# TSC_Project_v30.net
KiCad netlist of a schematic drawn in EAGLE
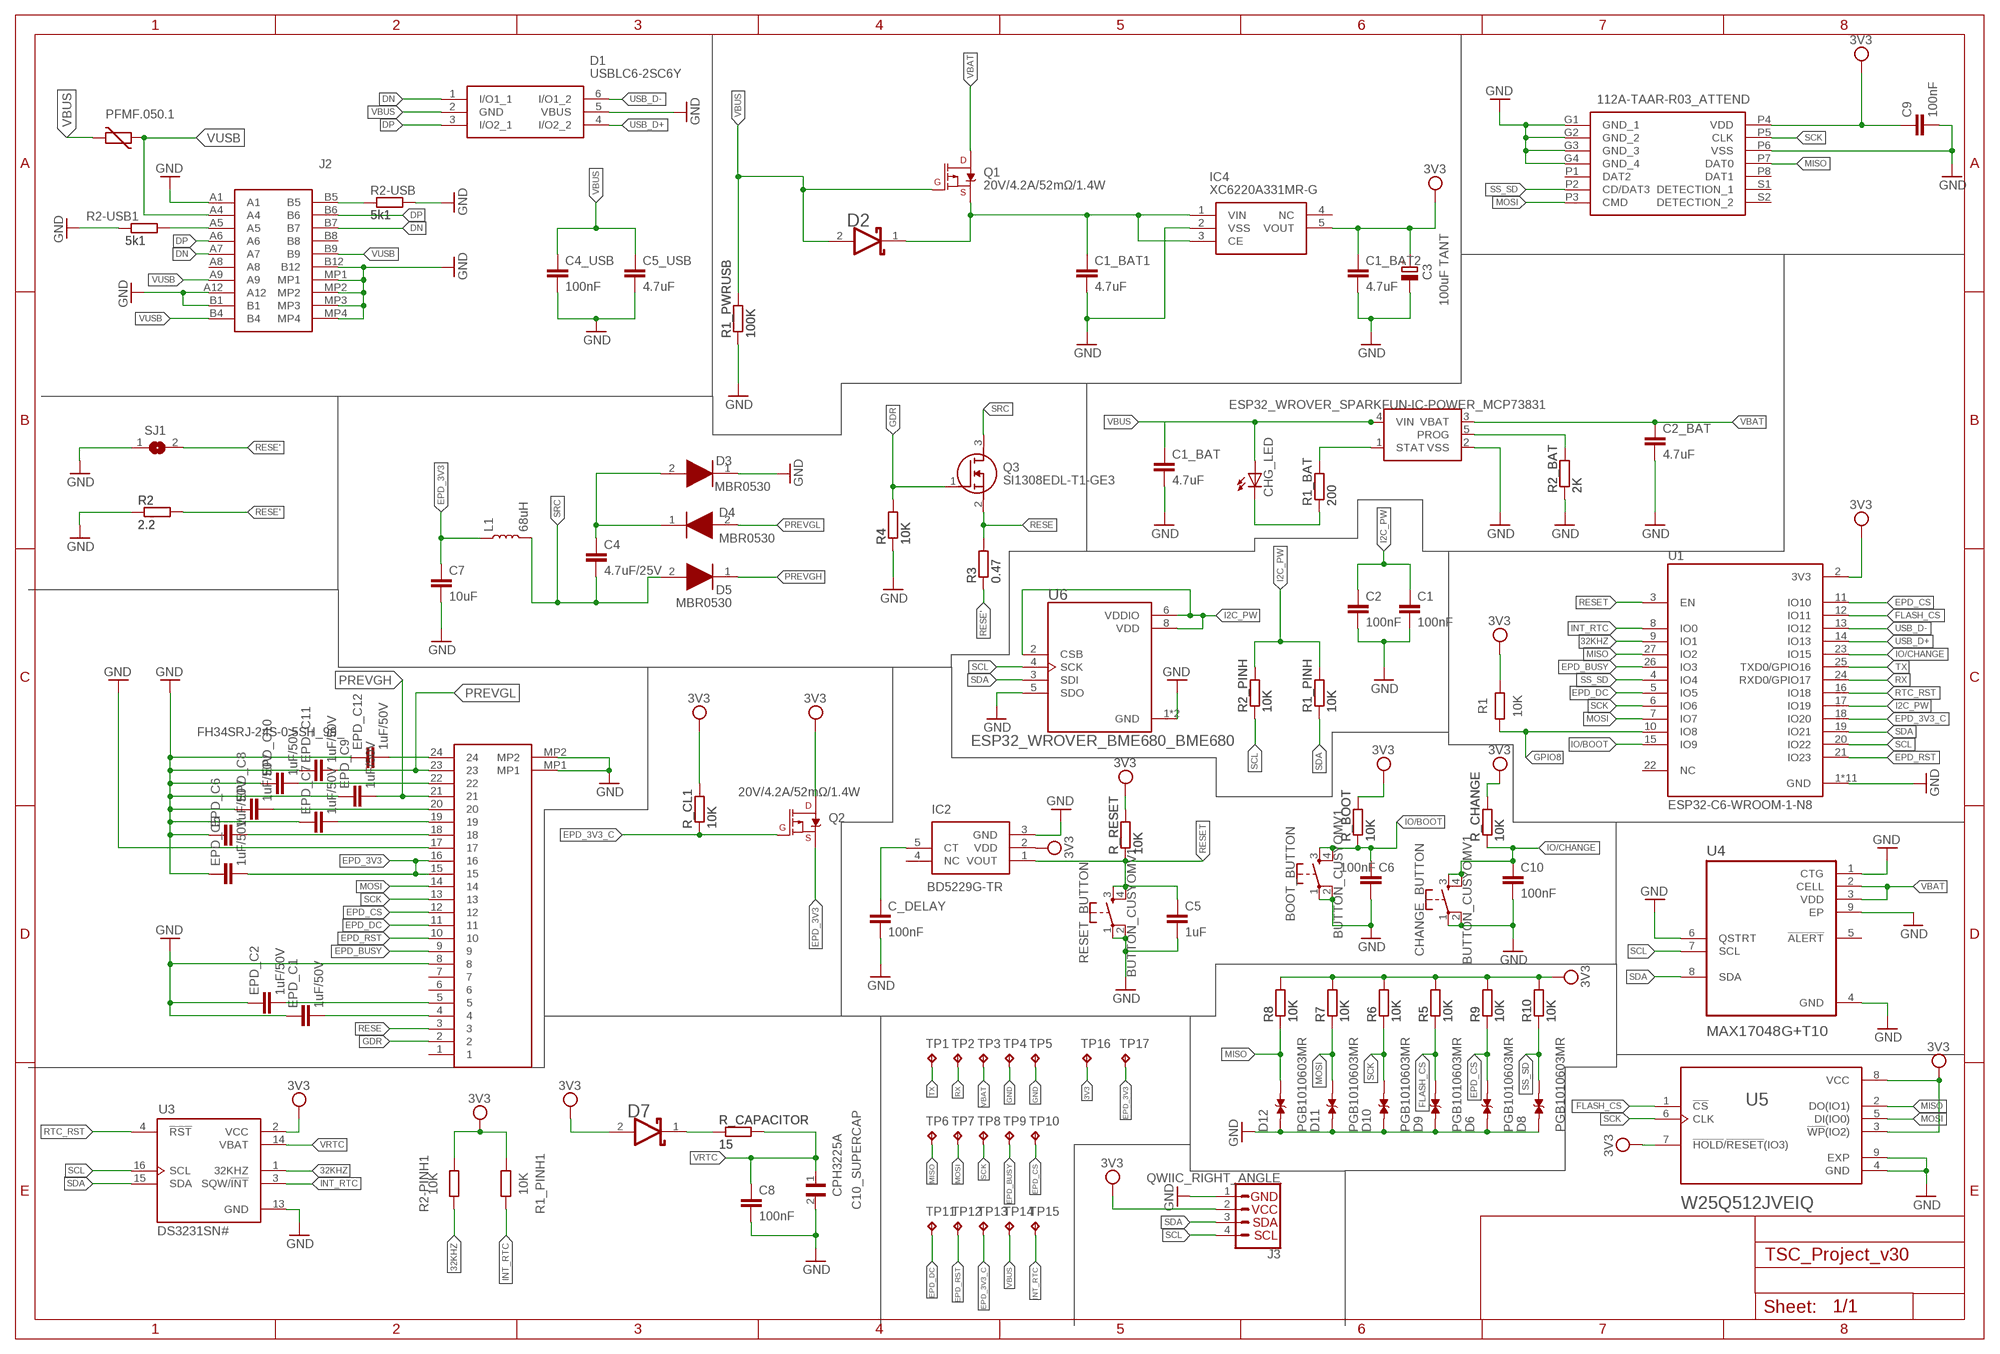
[diagram p0: schematic, sheet 1]

(export (version "E")
  (design (tool "Eeschema 10.0.6"))
  (components
    (comp (ref "BOOT_BUTTON")
      (value "BUTTON_CUSYOMV1")
      (footprint "eagle-import:MYBUTTON")
      (libsource (lib "eagle-import") (part "BUTTON_CUSYOMV1"))
    )
    (comp (ref "C1")
      (value "100nF")
      (footprint "eagle-import:ESP32_WROVER_EAGLE-LTSPICE_C0402")
      (libsource (lib "eagle-import") (part "ESP32_WROVER_EAGLE-LTSPICE_CC0402"))
    )
    (comp (ref "C1_BAT")
      (value "4.7uF")
      (footprint "eagle-import:ESP32_WROVER_EAGLE-LTSPICE_C0402")
      (libsource (lib "eagle-import") (part "ESP32_WROVER_EAGLE-LTSPICE_CC0402"))
    )
    (comp (ref "C1_BAT1")
      (value "4.7uF")
      (footprint "eagle-import:ESP32_WROVER_EAGLE-LTSPICE_C0402")
      (libsource (lib "eagle-import") (part "EAGLE-LTSPICE_CC0402"))
    )
    (comp (ref "C1_BAT2")
      (value "4.7uF")
      (footprint "eagle-import:ESP32_WROVER_EAGLE-LTSPICE_C0402")
      (libsource (lib "eagle-import") (part "EAGLE-LTSPICE_CC0402"))
    )
    (comp (ref "C2")
      (value "100nF")
      (footprint "eagle-import:ESP32_WROVER_EAGLE-LTSPICE_C0402")
      (libsource (lib "eagle-import") (part "ESP32_WROVER_EAGLE-LTSPICE_CC0402"))
    )
    (comp (ref "C2_BAT")
      (value "4.7uF")
      (footprint "eagle-import:ESP32_WROVER_EAGLE-LTSPICE_C0402")
      (libsource (lib "eagle-import") (part "ESP32_WROVER_EAGLE-LTSPICE_CC0402"))
    )
    (comp (ref "C3")
      (value "100uF TANT")
      (footprint "eagle-import:RCL_CT3528")
      (libsource (lib "eagle-import") (part "RCL_CPOL-EUCT3528"))
    )
    (comp (ref "C4")
      (value "4.7uF/25V")
      (footprint "eagle-import:ESP32_WROVER_EAGLE-LTSPICE_C0402")
      (libsource (lib "eagle-import") (part "ESP32_WROVER_EAGLE-LTSPICE_CC0402"))
    )
    (comp (ref "C4_USB")
      (value "100nF")
      (footprint "eagle-import:ESP32_WROVER_EAGLE-LTSPICE_C0402")
      (libsource (lib "eagle-import") (part "EAGLE-LTSPICE_CC0402"))
    )
    (comp (ref "C5")
      (value "1uF")
      (footprint "eagle-import:ESP32_WROVER_EAGLE-LTSPICE_C0402")
      (libsource (lib "eagle-import") (part "ESP32_WROVER_EAGLE-LTSPICE_CC0402"))
    )
    (comp (ref "C5_USB")
      (value "4.7uF")
      (footprint "eagle-import:ESP32_WROVER_EAGLE-LTSPICE_C0402")
      (libsource (lib "eagle-import") (part "EAGLE-LTSPICE_CC0402"))
    )
    (comp (ref "C6")
      (value "100nF")
      (footprint "eagle-import:ESP32_WROVER_EAGLE-LTSPICE_C0402")
      (libsource (lib "eagle-import") (part "ESP32_WROVER_EAGLE-LTSPICE_CC0402"))
    )
    (comp (ref "C7")
      (value "10uF")
      (footprint "eagle-import:ESP32_WROVER_EAGLE-LTSPICE_C0402")
      (libsource (lib "eagle-import") (part "ESP32_WROVER_EAGLE-LTSPICE_CC0402"))
    )
    (comp (ref "C8")
      (value "100nF")
      (footprint "eagle-import:ESP32_WROVER_EAGLE-LTSPICE_C0402")
      (libsource (lib "eagle-import") (part "ESP32_WROVER_EAGLE-LTSPICE_CC0402"))
    )
    (comp (ref "C9")
      (value "100nF")
      (footprint "eagle-import:ESP32_WROVER_EAGLE-LTSPICE_C0402")
      (libsource (lib "eagle-import") (part "ESP32_WROVER_EAGLE-LTSPICE_CC0402"))
    )
    (comp (ref "C10")
      (value "100nF")
      (footprint "eagle-import:ESP32_WROVER_EAGLE-LTSPICE_C0402")
      (libsource (lib "eagle-import") (part "ESP32_WROVER_EAGLE-LTSPICE_CC0402"))
    )
    (comp (ref "C10_SUPERCAP")
      (value "CPH3225A")
      (footprint "eagle-import:CAPCP3225X100N")
      (fields (field (name "MF") "Seiko Instruments"))
      (libsource (lib "eagle-import") (part "CPH3225A"))
    )
    (comp (ref "CHANGE_BUTTON")
      (value "BUTTON_CUSYOMV1")
      (footprint "eagle-import:MYBUTTON")
      (libsource (lib "eagle-import") (part "BUTTON_CUSYOMV1"))
    )
    (comp (ref "CHG_LED")
      (value "ADAFRUIT_LEDCHIP-LED0603")
      (footprint "eagle-import:ADAFRUIT_CHIP-LED0603")
      (libsource (lib "eagle-import") (part "ADAFRUIT_LEDCHIP-LED0603"))
    )
    (comp (ref "C_DELAY")
      (value "100nF")
      (footprint "eagle-import:ESP32_WROVER_EAGLE-LTSPICE_C0402")
      (libsource (lib "eagle-import") (part "EAGLE-LTSPICE_CC0402"))
    )
    (comp (ref "D1")
      (value "USBLC6-2SC6Y")
      (footprint "eagle-import:SOT95P280X145-6N")
      (fields (field (name "MF") "STMicroelectronics"))
      (libsource (lib "eagle-import") (part "USBLC6-2SC6Y"))
    )
    (comp (ref "D2")
      (value "ESP32_WROVER_AVX---SD0805S020S1R0_AVX_SD0805S020S1R0_0_0AVX_SD0805S020S1R0_0_0")
      (footprint "eagle-import:ESP32_WROVER_AVX---SD0805S020S1R0_AVX_SD0805S020S1R0_0")
      (fields
        (field (name "DIGIKEY_PART_NUMBER") "478-7800-1-ND")
        (field (name "MF") "AVX")
        (field (name "MOUSER_PART_NUMBER") "581-SD0805S020S1R0")
      )
      (libsource (lib "eagle-import") (part "ESP32_WROVER_AVX---SD0805S020S1R0_AVX_SD0805S020S1R0_0_0AVX_SD0805S020S1R0_0_0"))
    )
    (comp (ref "D3")
      (value "MBR0530")
      (footprint "eagle-import:SOD3716X135N")
      (fields (field (name "MF") "ON Semiconductor"))
      (libsource (lib "eagle-import") (part "MBR0530"))
    )
    (comp (ref "D4")
      (value "MBR0530")
      (footprint "eagle-import:SOD3716X135N")
      (fields (field (name "MF") "ON Semiconductor"))
      (libsource (lib "eagle-import") (part "MBR0530"))
    )
    (comp (ref "D5")
      (value "MBR0530")
      (footprint "eagle-import:SOD3716X135N")
      (fields (field (name "MF") "ON Semiconductor"))
      (libsource (lib "eagle-import") (part "MBR0530"))
    )
    (comp (ref "D6")
      (value "PGB1010603MR")
      (footprint "eagle-import:DIOC1608X36N")
      (fields (field (name "MF") "Littelfuse Inc."))
      (libsource (lib "eagle-import") (part "PGB1010603MR"))
    )
    (comp (ref "D7")
      (value "ESP32_WROVER_AVX---SD0805S020S1R0_AVX_SD0805S020S1R0_0_0AVX_SD0805S020S1R0_0_0")
      (footprint "eagle-import:ESP32_WROVER_AVX---SD0805S020S1R0_AVX_SD0805S020S1R0_0")
      (fields
        (field (name "DIGIKEY_PART_NUMBER") "478-7800-1-ND")
        (field (name "MF") "AVX")
        (field (name "MOUSER_PART_NUMBER") "581-SD0805S020S1R0")
      )
      (libsource (lib "eagle-import") (part "ESP32_WROVER_AVX---SD0805S020S1R0_AVX_SD0805S020S1R0_0_0AVX_SD0805S020S1R0_0_0"))
    )
    (comp (ref "D8")
      (value "PGB1010603MR")
      (footprint "eagle-import:DIOC1608X36N")
      (fields (field (name "MF") "Littelfuse Inc."))
      (libsource (lib "eagle-import") (part "PGB1010603MR"))
    )
    (comp (ref "D9")
      (value "PGB1010603MR")
      (footprint "eagle-import:DIOC1608X36N")
      (fields (field (name "MF") "Littelfuse Inc."))
      (libsource (lib "eagle-import") (part "PGB1010603MR"))
    )
    (comp (ref "D10")
      (value "PGB1010603MR")
      (footprint "eagle-import:DIOC1608X36N")
      (fields (field (name "MF") "Littelfuse Inc."))
      (libsource (lib "eagle-import") (part "PGB1010603MR"))
    )
    (comp (ref "D11")
      (value "PGB1010603MR")
      (footprint "eagle-import:DIOC1608X36N")
      (fields (field (name "MF") "Littelfuse Inc."))
      (libsource (lib "eagle-import") (part "PGB1010603MR"))
    )
    (comp (ref "D12")
      (value "PGB1010603MR")
      (footprint "eagle-import:DIOC1608X36N")
      (fields (field (name "MF") "Littelfuse Inc."))
      (libsource (lib "eagle-import") (part "PGB1010603MR"))
    )
    (comp (ref "EPD_C1")
      (value "1uF/50V")
      (footprint "eagle-import:ESP32_WROVER_EAGLE-LTSPICE_C0402")
      (libsource (lib "eagle-import") (part "ESP32_WROVER_EAGLE-LTSPICE_CC0402"))
    )
    (comp (ref "EPD_C2")
      (value "1uF/50V")
      (footprint "eagle-import:ESP32_WROVER_EAGLE-LTSPICE_C0402")
      (libsource (lib "eagle-import") (part "ESP32_WROVER_EAGLE-LTSPICE_CC0402"))
    )
    (comp (ref "EPD_C5")
      (value "1uF/50V")
      (footprint "eagle-import:ESP32_WROVER_EAGLE-LTSPICE_C0402")
      (libsource (lib "eagle-import") (part "ESP32_WROVER_EAGLE-LTSPICE_CC0402"))
    )
    (comp (ref "EPD_C6")
      (value "1uF/50V")
      (footprint "eagle-import:ESP32_WROVER_EAGLE-LTSPICE_C0402")
      (libsource (lib "eagle-import") (part "ESP32_WROVER_EAGLE-LTSPICE_CC0402"))
    )
    (comp (ref "EPD_C7")
      (value "1uF/50V")
      (footprint "eagle-import:ESP32_WROVER_EAGLE-LTSPICE_C0402")
      (libsource (lib "eagle-import") (part "ESP32_WROVER_EAGLE-LTSPICE_CC0402"))
    )
    (comp (ref "EPD_C8")
      (value "1uF/50V")
      (footprint "eagle-import:ESP32_WROVER_EAGLE-LTSPICE_C0402")
      (libsource (lib "eagle-import") (part "ESP32_WROVER_EAGLE-LTSPICE_CC0402"))
    )
    (comp (ref "EPD_C9")
      (value "1uF/50V")
      (footprint "eagle-import:ESP32_WROVER_EAGLE-LTSPICE_C0402")
      (libsource (lib "eagle-import") (part "ESP32_WROVER_EAGLE-LTSPICE_CC0402"))
    )
    (comp (ref "EPD_C10")
      (value "1uF/50V")
      (footprint "eagle-import:ESP32_WROVER_EAGLE-LTSPICE_C0402")
      (libsource (lib "eagle-import") (part "ESP32_WROVER_EAGLE-LTSPICE_CC0402"))
    )
    (comp (ref "EPD_C11")
      (value "1uF/50V")
      (footprint "eagle-import:ESP32_WROVER_EAGLE-LTSPICE_C0402")
      (libsource (lib "eagle-import") (part "ESP32_WROVER_EAGLE-LTSPICE_CC0402"))
    )
    (comp (ref "EPD_C12")
      (value "1uF/50V")
      (footprint "eagle-import:ESP32_WROVER_EAGLE-LTSPICE_C0402")
      (libsource (lib "eagle-import") (part "ESP32_WROVER_EAGLE-LTSPICE_CC0402"))
    )
    (comp (ref "IC2")
      (value "BD5229G-TR")
      (footprint "eagle-import:SOT95P280X125-5N")
      (fields (field (name "MOUSER_PART_NUMBER") "755-BD5229G-TR"))
      (libsource (lib "eagle-import") (part "BD5229G-TR"))
    )
    (comp (ref "IC4")
      (value "XC6220A331MR-G")
      (footprint "eagle-import:SOT95P280X120-5N")
      (fields (field (name "MOUSER_PART_NUMBER") "865-XC6220A331MR-G"))
      (libsource (lib "eagle-import") (part "XC6220A331MR-G"))
    )
    (comp (ref "J1")
      (value "FH34SRJ-24S-0.5SH_99_")
      (footprint "eagle-import:FH34SRJ24S05SH99")
      (fields
        (field (name "MANUFACTURER_PART_NUMBER") "FH34SRJ-24S-0.5SH(99)")
        (field (name "MOUSER_PART_NUMBER") "798-FH34SRJ24S05SH99")
      )
      (libsource (lib "eagle-import") (part "FH34SRJ-24S-0.5SH_99_"))
    )
    (comp (ref "J2")
      (value "SAMACSYS_PARTS_USB4110-GF-A")
      (footprint "eagle-import:SAMACSYS_PARTS_USB4110GFA")
      (fields
        (field (name "MANUFACTURER_PART_NUMBER") "USB4110-GF-A")
        (field (name "MOUSER_PART_NUMBER") "640-USB4110-GF-A")
      )
      (libsource (lib "eagle-import") (part "SAMACSYS_PARTS_USB4110-GF-A"))
    )
    (comp (ref "J3")
      (value "QWIIC_RIGHT_ANGLE")
      (footprint "eagle-import:JST04_1MM_RA")
      (libsource (lib "eagle-import") (part "QWIIC_CONNECTORJS-1MM"))
    )
    (comp (ref "J4")
      (value "112A-TAAR-R03_ATTEND")
      (footprint "eagle-import:112ATAARR03ATTEND")
      (fields (field (name "MANUFACTURER_PART_NUMBER") "112A-TAAR-R03 ATTEND"))
      (libsource (lib "eagle-import") (part "112A-TAAR-R03_ATTEND"))
    )
    (comp (ref "L1")
      (value "68uH")
      (footprint "eagle-import:CR75")
      (libsource (lib "eagle-import") (part "INDUCTOR-CR75-68UH"))
    )
    (comp (ref "PFMF.050.1")
      (value "ESP32C6_VARISTORCN1812")
      (footprint "eagle-import:ESP32C6_VARISTOR_CT_CN1812")
      (libsource (lib "eagle-import") (part "ESP32C6_VARISTORCN1812"))
    )
    (comp (ref "Q1")
      (value "20V/4.2A/52mΩ/1.4W")
      (footprint "eagle-import:ESP32_WROVER_SPARKFUN-DISCRETESEMI_SOT23-3")
      (libsource (lib "eagle-import") (part "ESP32_WROVER_SPARKFUN-DISCRETESEMI_MOSFET_PCH-DMG2305UX-7"))
    )
    (comp (ref "Q2")
      (value "20V/4.2A/52mΩ/1.4W")
      (footprint "eagle-import:ESP32_WROVER_SPARKFUN-DISCRETESEMI_SOT23-3")
      (libsource (lib "eagle-import") (part "ESP32_WROVER_SPARKFUN-DISCRETESEMI_MOSFET_PCH-DMG2305UX-7"))
    )
    (comp (ref "Q3")
      (value "SI1308EDL-T1-GE3")
      (footprint "eagle-import:SOT65P210X110-3N")
      (fields (field (name "MF") "Vishay Siliconix"))
      (libsource (lib "eagle-import") (part "SI1308EDL-T1-GE3"))
    )
    (comp (ref "R1")
      (value "10K")
      (footprint "eagle-import:ESP32_WROVER_EAGLE-LTSPICE_R0402")
      (libsource (lib "eagle-import") (part "ESP32_WROVER_EAGLE-LTSPICE_RR0402"))
    )
    (comp (ref "R1_BAT")
      (value "200")
      (footprint "eagle-import:ESP32_WROVER_EAGLE-LTSPICE_R0402")
      (libsource (lib "eagle-import") (part "ESP32_WROVER_EAGLE-LTSPICE_RR0402"))
    )
    (comp (ref "R1_PINH")
      (value "10K")
      (footprint "eagle-import:ESP32_WROVER_EAGLE-LTSPICE_R0402")
      (libsource (lib "eagle-import") (part "ESP32_WROVER_EAGLE-LTSPICE_RR0402"))
    )
    (comp (ref "R1_PINH1")
      (value "10K")
      (footprint "eagle-import:ESP32_WROVER_EAGLE-LTSPICE_R0402")
      (libsource (lib "eagle-import") (part "ESP32_WROVER_EAGLE-LTSPICE_RR0402"))
    )
    (comp (ref "R1_PWRUSB")
      (value "100K")
      (footprint "eagle-import:ESP32_WROVER_EAGLE-LTSPICE_R0402")
      (libsource (lib "eagle-import") (part "ESP32_WROVER_EAGLE-LTSPICE_RR0402"))
    )
    (comp (ref "R2")
      (value "2.2")
      (footprint "eagle-import:ESP32_WROVER_EAGLE-LTSPICE_R0402")
      (libsource (lib "eagle-import") (part "ESP32_WROVER_EAGLE-LTSPICE_RR0402"))
    )
    (comp (ref "R2-PINH1")
      (value "10K")
      (footprint "eagle-import:ESP32_WROVER_EAGLE-LTSPICE_R0402")
      (libsource (lib "eagle-import") (part "ESP32_WROVER_EAGLE-LTSPICE_RR0402"))
    )
    (comp (ref "R2-USB")
      (value "5k1")
      (footprint "eagle-import:ESP32_WROVER_EAGLE-LTSPICE_R0402")
      (libsource (lib "eagle-import") (part "ESP32_WROVER_EAGLE-LTSPICE_RR0402"))
    )
    (comp (ref "R2-USB1")
      (value "5k1")
      (footprint "eagle-import:ESP32_WROVER_EAGLE-LTSPICE_R0402")
      (libsource (lib "eagle-import") (part "ESP32_WROVER_EAGLE-LTSPICE_RR0402"))
    )
    (comp (ref "R2_BAT")
      (value "2K")
      (footprint "eagle-import:ESP32_WROVER_EAGLE-LTSPICE_R0402")
      (libsource (lib "eagle-import") (part "ESP32_WROVER_EAGLE-LTSPICE_RR0402"))
    )
    (comp (ref "R2_PINH")
      (value "10K")
      (footprint "eagle-import:ESP32_WROVER_EAGLE-LTSPICE_R0402")
      (libsource (lib "eagle-import") (part "ESP32_WROVER_EAGLE-LTSPICE_RR0402"))
    )
    (comp (ref "R3")
      (value "0.47")
      (footprint "eagle-import:ESP32_WROVER_EAGLE-LTSPICE_R0402")
      (libsource (lib "eagle-import") (part "ESP32_WROVER_EAGLE-LTSPICE_RR0402"))
    )
    (comp (ref "R4")
      (value "10K")
      (footprint "eagle-import:ESP32_WROVER_EAGLE-LTSPICE_R0402")
      (libsource (lib "eagle-import") (part "ESP32_WROVER_EAGLE-LTSPICE_RR0402"))
    )
    (comp (ref "R5")
      (value "10K")
      (footprint "eagle-import:ESP32_WROVER_EAGLE-LTSPICE_R0402")
      (libsource (lib "eagle-import") (part "ESP32_WROVER_EAGLE-LTSPICE_RR0402"))
    )
    (comp (ref "R6")
      (value "10K")
      (footprint "eagle-import:ESP32_WROVER_EAGLE-LTSPICE_R0402")
      (libsource (lib "eagle-import") (part "ESP32_WROVER_EAGLE-LTSPICE_RR0402"))
    )
    (comp (ref "R7")
      (value "10K")
      (footprint "eagle-import:ESP32_WROVER_EAGLE-LTSPICE_R0402")
      (libsource (lib "eagle-import") (part "ESP32_WROVER_EAGLE-LTSPICE_RR0402"))
    )
    (comp (ref "R8")
      (value "10K")
      (footprint "eagle-import:ESP32_WROVER_EAGLE-LTSPICE_R0402")
      (libsource (lib "eagle-import") (part "ESP32_WROVER_EAGLE-LTSPICE_RR0402"))
    )
    (comp (ref "R9")
      (value "10K")
      (footprint "eagle-import:ESP32_WROVER_EAGLE-LTSPICE_R0402")
      (libsource (lib "eagle-import") (part "ESP32_WROVER_EAGLE-LTSPICE_RR0402"))
    )
    (comp (ref "R10")
      (value "10K")
      (footprint "eagle-import:ESP32_WROVER_EAGLE-LTSPICE_R0402")
      (libsource (lib "eagle-import") (part "ESP32_WROVER_EAGLE-LTSPICE_RR0402"))
    )
    (comp (ref "RESET_BUTTON")
      (value "BUTTON_CUSYOMV1")
      (footprint "eagle-import:MYBUTTON")
      (libsource (lib "eagle-import") (part "BUTTON_CUSYOMV1"))
    )
    (comp (ref "R_BOOT")
      (value "10K")
      (footprint "eagle-import:ESP32_WROVER_EAGLE-LTSPICE_R0402")
      (libsource (lib "eagle-import") (part "ESP32_WROVER_EAGLE-LTSPICE_RR0402"))
    )
    (comp (ref "R_CAPACITOR")
      (value "15")
      (footprint "eagle-import:ESP32_WROVER_EAGLE-LTSPICE_R0402")
      (libsource (lib "eagle-import") (part "ESP32_WROVER_EAGLE-LTSPICE_RR0402"))
    )
    (comp (ref "R_CHANGE")
      (value "10K")
      (footprint "eagle-import:ESP32_WROVER_EAGLE-LTSPICE_R0402")
      (libsource (lib "eagle-import") (part "ESP32_WROVER_EAGLE-LTSPICE_RR0402"))
    )
    (comp (ref "R_CL1")
      (value "10K")
      (footprint "eagle-import:ESP32_WROVER_EAGLE-LTSPICE_R0402")
      (libsource (lib "eagle-import") (part "ESP32_WROVER_EAGLE-LTSPICE_RR0402"))
    )
    (comp (ref "R_RESET")
      (value "10K")
      (footprint "eagle-import:ESP32_WROVER_EAGLE-LTSPICE_R0402")
      (libsource (lib "eagle-import") (part "ESP32_WROVER_EAGLE-LTSPICE_RR0402"))
    )
    (comp (ref "SJ1") (value "SJ") (footprint "eagle-import:SJ") (libsource (lib "eagle-import") (part "SJ")))
    (comp (ref "TP1")
      (value "TPTP20R")
      (footprint "eagle-import:TP20R")
      (libsource (lib "eagle-import") (part "TPTP20R"))
    )
    (comp (ref "TP2")
      (value "TPTP20R")
      (footprint "eagle-import:TP20R")
      (libsource (lib "eagle-import") (part "TPTP20R"))
    )
    (comp (ref "TP3")
      (value "TPTP20R")
      (footprint "eagle-import:TP20R")
      (libsource (lib "eagle-import") (part "TPTP20R"))
    )
    (comp (ref "TP4")
      (value "TPTP20R")
      (footprint "eagle-import:TP20R")
      (libsource (lib "eagle-import") (part "TPTP20R"))
    )
    (comp (ref "TP5")
      (value "TPTP20R")
      (footprint "eagle-import:TP20R")
      (libsource (lib "eagle-import") (part "TPTP20R"))
    )
    (comp (ref "TP6")
      (value "TPTP20R")
      (footprint "eagle-import:TP20R")
      (libsource (lib "eagle-import") (part "TPTP20R"))
    )
    (comp (ref "TP7")
      (value "TPTP20R")
      (footprint "eagle-import:TP20R")
      (libsource (lib "eagle-import") (part "TPTP20R"))
    )
    (comp (ref "TP8")
      (value "TPTP20R")
      (footprint "eagle-import:TP20R")
      (libsource (lib "eagle-import") (part "TPTP20R"))
    )
    (comp (ref "TP9")
      (value "TPTP20R")
      (footprint "eagle-import:TP20R")
      (libsource (lib "eagle-import") (part "TPTP20R"))
    )
    (comp (ref "TP10")
      (value "TPTP20R")
      (footprint "eagle-import:TP20R")
      (libsource (lib "eagle-import") (part "TPTP20R"))
    )
    (comp (ref "TP11")
      (value "TPTP20R")
      (footprint "eagle-import:TP20R")
      (libsource (lib "eagle-import") (part "TPTP20R"))
    )
    (comp (ref "TP12")
      (value "TPTP20R")
      (footprint "eagle-import:TP20R")
      (libsource (lib "eagle-import") (part "TPTP20R"))
    )
    (comp (ref "TP13")
      (value "TPTP20R")
      (footprint "eagle-import:TP20R")
      (libsource (lib "eagle-import") (part "TPTP20R"))
    )
    (comp (ref "TP14")
      (value "TPTP20R")
      (footprint "eagle-import:TP20R")
      (libsource (lib "eagle-import") (part "TPTP20R"))
    )
    (comp (ref "TP15")
      (value "TPTP20R")
      (footprint "eagle-import:TP20R")
      (libsource (lib "eagle-import") (part "TPTP20R"))
    )
    (comp (ref "TP16")
      (value "TPTP20R")
      (footprint "eagle-import:TP20R")
      (libsource (lib "eagle-import") (part "TPTP20R"))
    )
    (comp (ref "TP17")
      (value "TPTP20R")
      (footprint "eagle-import:TP20R")
      (libsource (lib "eagle-import") (part "TPTP20R"))
    )
    (comp (ref "U1")
      (value "ESP32-C6-WROOM-1-N8")
      (footprint "eagle-import:XCVR_ESP32-C6-WROOM-1-N8")
      (fields (field (name "MF") "Espressif Systems"))
      (libsource (lib "eagle-import") (part "ESP32-C6-WROOM-1-N8"))
    )
    (comp (ref "U2")
      (value "ESP32_WROVER_SPARKFUN-IC-POWER_MCP73831")
      (footprint "eagle-import:ESP32_WROVER_SPARKFUN-IC-POWER_SOT23-5")
      (libsource (lib "eagle-import") (part "ESP32_WROVER_SPARKFUN-IC-POWER_MCP73831"))
    )
    (comp (ref "U3")
      (value "DS3231SN#")
      (footprint "eagle-import:SOIC127P1032X265-16N")
      (fields (field (name "MF") "Analog Devices"))
      (libsource (lib "eagle-import") (part "DS3231SN#"))
    )
    (comp (ref "U4")
      (value "MAX17048G+T10")
      (footprint "eagle-import:SON50P200X200X80-9N")
      (fields (field (name "MF") "Analog Devices"))
      (libsource (lib "eagle-import") (part "MAX17048G+T10"))
    )
    (comp (ref "U5")
      (value "W25Q512JVEIQ")
      (footprint "eagle-import:SON127P600X800X80-9N")
      (fields (field (name "MF") "Winbond Electronics"))
      (libsource (lib "eagle-import") (part "W25Q512JVEIQ"))
    )
    (comp (ref "U6")
      (value "ESP32_WROVER_BME680_BME680")
      (footprint "eagle-import:ESP32_WROVER_BME680_PSON80P300X300X100-8N")
      (fields (field (name "MF") "Bosch Sensortec") (field (name "MP") "BME680"))
      (libsource (lib "eagle-import") (part "ESP32_WROVER_BME680_BME680"))
    )
  )
  (nets
    (net (code "1") (name "3V3") (class "Default")
      (node (ref "C1_BAT2") (pin "1") (pinfunction "1_1") (pintype "passive"))
      (node (ref "C3") (pin "+") (pinfunction "+_+") (pintype "passive"))
      (node (ref "C9") (pin "1") (pinfunction "1_1") (pintype "passive"))
      (node (ref "D7") (pin "2") (pinfunction "ANODE_2") (pintype "bidirectional"))
      (node (ref "IC2") (pin "2") (pinfunction "VDD_2") (pintype "bidirectional"))
      (node (ref "IC4") (pin "5") (pinfunction "VOUT_5") (pintype "bidirectional"))
      (node (ref "J3") (pin "2") (pinfunction "2_2") (pintype "power_in"))
      (node (ref "J4") (pin "P4") (pinfunction "VDD_P4") (pintype "bidirectional"))
      (node (ref "Q2") (pin "3") (pinfunction "D_3") (pintype "bidirectional"))
      (node (ref "R1") (pin "2") (pinfunction "2_2") (pintype "passive"))
      (node (ref "R10") (pin "2") (pinfunction "2_2") (pintype "passive"))
      (node (ref "R1_PINH1") (pin "2") (pinfunction "2_2") (pintype "passive"))
      (node (ref "R2-PINH1") (pin "2") (pinfunction "2_2") (pintype "passive"))
      (node (ref "R5") (pin "2") (pinfunction "2_2") (pintype "passive"))
      (node (ref "R6") (pin "2") (pinfunction "2_2") (pintype "passive"))
      (node (ref "R7") (pin "2") (pinfunction "2_2") (pintype "passive"))
      (node (ref "R8") (pin "2") (pinfunction "2_2") (pintype "passive"))
      (node (ref "R9") (pin "2") (pinfunction "2_2") (pintype "passive"))
      (node (ref "R_BOOT") (pin "2") (pinfunction "2_2") (pintype "passive"))
      (node (ref "R_CHANGE") (pin "2") (pinfunction "2_2") (pintype "passive"))
      (node (ref "R_CL1") (pin "2") (pinfunction "2_2") (pintype "passive"))
      (node (ref "R_RESET") (pin "2") (pinfunction "2_2") (pintype "passive"))
      (node (ref "TP16") (pin "TP") (pinfunction "TP_TP") (pintype "input"))
      (node (ref "U1") (pin "2") (pinfunction "3V3_2") (pintype "power_in"))
      (node (ref "U3") (pin "2") (pinfunction "VCC_2") (pintype "power_in"))
      (node (ref "U5") (pin "3") (pinfunction "~{WP}(IO2)_3") (pintype "bidirectional"))
      (node (ref "U5") (pin "7") (pinfunction "~{HOLD}/~{RESET}(IO3)_7") (pintype "bidirectional"))
      (node (ref "U5") (pin "8") (pinfunction "VCC_8") (pintype "power_in"))
    )
    (net (code "2") (name "32KHZ") (class "Default")
      (node (ref "R2-PINH1") (pin "1") (pinfunction "1_1") (pintype "passive"))
      (node (ref "U1") (pin "9") (pinfunction "IO1_9") (pintype "bidirectional"))
      (node (ref "U3") (pin "1") (pinfunction "32KHZ_1") (pintype "output"))
    )
    (net (code "3") (name "DN") (class "Default")
      (node (ref "D1") (pin "1") (pinfunction "I/O1_1_1") (pintype "bidirectional"))
      (node (ref "J2") (pin "A7") (pinfunction "A7_A7") (pintype "bidirectional"))
      (node (ref "J2") (pin "B7") (pinfunction "B7_B7") (pintype "bidirectional"))
    )
    (net (code "4") (name "DP") (class "Default")
      (node (ref "D1") (pin "3") (pinfunction "I/O2_1_3") (pintype "bidirectional"))
      (node (ref "J2") (pin "A6") (pinfunction "A6_A6") (pintype "bidirectional"))
      (node (ref "J2") (pin "B6") (pinfunction "B6_B6") (pintype "bidirectional"))
    )
    (net (code "5") (name "EPD_3V3") (class "Default")
      (node (ref "C7") (pin "1") (pinfunction "1_1") (pintype "passive"))
      (node (ref "EPD_C5") (pin "2") (pinfunction "2_2") (pintype "passive"))
      (node (ref "J1") (pin "15") (pinfunction "15_15") (pintype "bidirectional"))
      (node (ref "J1") (pin "16") (pinfunction "16_16") (pintype "bidirectional"))
      (node (ref "L1") (pin "P$1") (pinfunction "1_P$1") (pintype "passive"))
      (node (ref "Q2") (pin "2") (pinfunction "S_2") (pintype "bidirectional"))
      (node (ref "TP17") (pin "TP") (pinfunction "TP_TP") (pintype "input"))
    )
    (net (code "6") (name "EPD_3V3_C") (class "Default")
      (node (ref "Q2") (pin "1") (pinfunction "G_1") (pintype "bidirectional"))
      (node (ref "R_CL1") (pin "1") (pinfunction "1_1") (pintype "passive"))
      (node (ref "TP13") (pin "TP") (pinfunction "TP_TP") (pintype "input"))
      (node (ref "U1") (pin "18") (pinfunction "IO20_18") (pintype "bidirectional"))
    )
    (net (code "7") (name "EPD_BUSY") (class "Default")
      (node (ref "J1") (pin "9") (pinfunction "9_9") (pintype "bidirectional"))
      (node (ref "TP9") (pin "TP") (pinfunction "TP_TP") (pintype "input"))
      (node (ref "U1") (pin "26") (pinfunction "IO3_26") (pintype "bidirectional"))
    )
    (net (code "8") (name "EPD_CS") (class "Default")
      (node (ref "D6") (pin "2") (pinfunction "2_2") (pintype "passive"))
      (node (ref "J1") (pin "12") (pinfunction "12_12") (pintype "bidirectional"))
      (node (ref "R9") (pin "1") (pinfunction "1_1") (pintype "passive"))
      (node (ref "TP10") (pin "TP") (pinfunction "TP_TP") (pintype "input"))
      (node (ref "U1") (pin "11") (pinfunction "IO10_11") (pintype "bidirectional"))
    )
    (net (code "9") (name "EPD_DC") (class "Default")
      (node (ref "J1") (pin "11") (pinfunction "11_11") (pintype "bidirectional"))
      (node (ref "TP11") (pin "TP") (pinfunction "TP_TP") (pintype "input"))
      (node (ref "U1") (pin "5") (pinfunction "IO5_5") (pintype "bidirectional"))
    )
    (net (code "10") (name "EPD_RST") (class "Default")
      (node (ref "J1") (pin "10") (pinfunction "10_10") (pintype "bidirectional"))
      (node (ref "TP12") (pin "TP") (pinfunction "TP_TP") (pintype "input"))
      (node (ref "U1") (pin "21") (pinfunction "IO23_21") (pintype "bidirectional"))
    )
    (net (code "11") (name "FLASH_CS") (class "Default")
      (node (ref "D9") (pin "2") (pinfunction "2_2") (pintype "passive"))
      (node (ref "R5") (pin "1") (pinfunction "1_1") (pintype "passive"))
      (node (ref "U1") (pin "12") (pinfunction "IO11_12") (pintype "bidirectional"))
      (node (ref "U5") (pin "1") (pinfunction "~{CS}_1") (pintype "input"))
    )
    (net (code "12") (name "GDR") (class "Default")
      (node (ref "J1") (pin "2") (pinfunction "2_2") (pintype "bidirectional"))
      (node (ref "Q3") (pin "1") (pinfunction "G_1") (pintype "bidirectional"))
      (node (ref "R4") (pin "2") (pinfunction "2_2") (pintype "passive"))
    )
    (net (code "13") (name "GND") (class "Default")
      (node (ref "BOOT_BUTTON") (pin "1") (pinfunction "1_1") (pintype "passive"))
      (node (ref "BOOT_BUTTON") (pin "2") (pinfunction "2_2") (pintype "passive"))
      (node (ref "C1") (pin "2") (pinfunction "2_2") (pintype "passive"))
      (node (ref "C10") (pin "2") (pinfunction "2_2") (pintype "passive"))
      (node (ref "C10_SUPERCAP") (pin "2") (pinfunction "2_2") (pintype "passive"))
      (node (ref "C1_BAT") (pin "2") (pinfunction "2_2") (pintype "passive"))
      (node (ref "C1_BAT1") (pin "2") (pinfunction "2_2") (pintype "passive"))
      (node (ref "C1_BAT2") (pin "2") (pinfunction "2_2") (pintype "passive"))
      (node (ref "C2") (pin "2") (pinfunction "2_2") (pintype "passive"))
      (node (ref "C2_BAT") (pin "2") (pinfunction "2_2") (pintype "passive"))
      (node (ref "C3") (pin "-") (pinfunction "-_-") (pintype "passive"))
      (node (ref "C4_USB") (pin "2") (pinfunction "2_2") (pintype "passive"))
      (node (ref "C5") (pin "2") (pinfunction "2_2") (pintype "passive"))
      (node (ref "C5_USB") (pin "2") (pinfunction "2_2") (pintype "passive"))
      (node (ref "C6") (pin "2") (pinfunction "2_2") (pintype "passive"))
      (node (ref "C7") (pin "2") (pinfunction "2_2") (pintype "passive"))
      (node (ref "C8") (pin "2") (pinfunction "2_2") (pintype "passive"))
      (node (ref "C9") (pin "2") (pinfunction "2_2") (pintype "passive"))
      (node (ref "CHANGE_BUTTON") (pin "1") (pinfunction "1_1") (pintype "passive"))
      (node (ref "CHANGE_BUTTON") (pin "2") (pinfunction "2_2") (pintype "passive"))
      (node (ref "C_DELAY") (pin "2") (pinfunction "2_2") (pintype "passive"))
      (node (ref "D1") (pin "5") (pinfunction "VBUS_5") (pintype "bidirectional"))
      (node (ref "D10") (pin "1") (pinfunction "1_1") (pintype "passive"))
      (node (ref "D11") (pin "1") (pinfunction "1_1") (pintype "passive"))
      (node (ref "D12") (pin "1") (pinfunction "1_1") (pintype "passive"))
      (node (ref "D3") (pin "1") (pinfunction "K_1") (pintype "bidirectional"))
      (node (ref "D6") (pin "1") (pinfunction "1_1") (pintype "passive"))
      (node (ref "D8") (pin "1") (pinfunction "1_1") (pintype "passive"))
      (node (ref "D9") (pin "1") (pinfunction "1_1") (pintype "passive"))
      (node (ref "EPD_C1") (pin "1") (pinfunction "1_1") (pintype "passive"))
      (node (ref "EPD_C10") (pin "1") (pinfunction "1_1") (pintype "passive"))
      (node (ref "EPD_C11") (pin "1") (pinfunction "1_1") (pintype "passive"))
      (node (ref "EPD_C12") (pin "1") (pinfunction "1_1") (pintype "passive"))
      (node (ref "EPD_C2") (pin "1") (pinfunction "1_1") (pintype "passive"))
      (node (ref "EPD_C5") (pin "1") (pinfunction "1_1") (pintype "passive"))
      (node (ref "EPD_C6") (pin "1") (pinfunction "1_1") (pintype "passive"))
      (node (ref "EPD_C7") (pin "1") (pinfunction "1_1") (pintype "passive"))
      (node (ref "EPD_C8") (pin "1") (pinfunction "1_1") (pintype "passive"))
      (node (ref "EPD_C9") (pin "1") (pinfunction "1_1") (pintype "passive"))
      (node (ref "IC2") (pin "3") (pinfunction "GND_3") (pintype "bidirectional"))
      (node (ref "IC4") (pin "2") (pinfunction "VSS_2") (pintype "bidirectional"))
      (node (ref "J1") (pin "17") (pinfunction "17_17") (pintype "bidirectional"))
      (node (ref "J1") (pin "8") (pinfunction "8_8") (pintype "bidirectional"))
      (node (ref "J1") (pin "MP1") (pinfunction "MP1_MP1") (pintype "bidirectional"))
      (node (ref "J1") (pin "MP2") (pinfunction "MP2_MP2") (pintype "bidirectional"))
      (node (ref "J2") (pin "A1") (pinfunction "A1_A1") (pintype "bidirectional"))
      (node (ref "J2") (pin "A12") (pinfunction "A12_A12") (pintype "bidirectional"))
      (node (ref "J2") (pin "B1") (pinfunction "B1_B1") (pintype "bidirectional"))
      (node (ref "J2") (pin "B12") (pinfunction "B12_B12") (pintype "bidirectional"))
      (node (ref "J2") (pin "MP1") (pinfunction "MP1_MP1") (pintype "bidirectional"))
      (node (ref "J2") (pin "MP2") (pinfunction "MP2_MP2") (pintype "bidirectional"))
      (node (ref "J2") (pin "MP3") (pinfunction "MP3_MP3") (pintype "bidirectional"))
      (node (ref "J2") (pin "MP4") (pinfunction "MP4_MP4") (pintype "bidirectional"))
      (node (ref "J3") (pin "1") (pinfunction "1_1") (pintype "power_in"))
      (node (ref "J4") (pin "G1") (pinfunction "GND_1_G1") (pintype "bidirectional"))
      (node (ref "J4") (pin "G2") (pinfunction "GND_2_G2") (pintype "bidirectional"))
      (node (ref "J4") (pin "G3") (pinfunction "GND_3_G3") (pintype "bidirectional"))
      (node (ref "J4") (pin "G4") (pinfunction "GND_4_G4") (pintype "bidirectional"))
      (node (ref "J4") (pin "P6") (pinfunction "VSS_P6") (pintype "bidirectional"))
      (node (ref "R1_PWRUSB") (pin "1") (pinfunction "1_1") (pintype "passive"))
      (node (ref "R2") (pin "1") (pinfunction "1_1") (pintype "passive"))
      (node (ref "R2-USB") (pin "2") (pinfunction "2_2") (pintype "passive"))
      (node (ref "R2-USB1") (pin "1") (pinfunction "1_1") (pintype "passive"))
      (node (ref "R2_BAT") (pin "1") (pinfunction "1_1") (pintype "passive"))
      (node (ref "R4") (pin "1") (pinfunction "1_1") (pintype "passive"))
      (node (ref "RESET_BUTTON") (pin "1") (pinfunction "1_1") (pintype "passive"))
      (node (ref "RESET_BUTTON") (pin "2") (pinfunction "2_2") (pintype "passive"))
      (node (ref "SJ1") (pin "1") (pinfunction "1_1") (pintype "passive"))
      (node (ref "TP4") (pin "TP") (pinfunction "TP_TP") (pintype "input"))
      (node (ref "TP5") (pin "TP") (pinfunction "TP_TP") (pintype "input"))
      (node (ref "U1") (pin "1") (pinfunction "GND_1") (pintype "power_in"))
      (node (ref "U1") (pin "28") (pinfunction "GND_28") (pintype "power_in"))
      (node (ref "U1") (pin "29_1") (pinfunction "GND_29_1") (pintype "power_in"))
      (node (ref "U1") (pin "29_2") (pinfunction "GND_29_2") (pintype "power_in"))
      (node (ref "U1") (pin "29_3") (pinfunction "GND_29_3") (pintype "power_in"))
      (node (ref "U1") (pin "29_4") (pinfunction "GND_29_4") (pintype "power_in"))
      (node (ref "U1") (pin "29_5") (pinfunction "GND_29_5") (pintype "power_in"))
      (node (ref "U1") (pin "29_6") (pinfunction "GND_29_6") (pintype "power_in"))
      (node (ref "U1") (pin "29_7") (pinfunction "GND_29_7") (pintype "power_in"))
      (node (ref "U1") (pin "29_8") (pinfunction "GND_29_8") (pintype "power_in"))
      (node (ref "U1") (pin "29_9") (pinfunction "GND_29_9") (pintype "power_in"))
      (node (ref "U2") (pin "2") (pinfunction "VSS_2") (pintype "power_in"))
      (node (ref "U3") (pin "13") (pinfunction "GND_13") (pintype "power_in"))
      (node (ref "U4") (pin "1") (pinfunction "CTG_1") (pintype "power_in"))
      (node (ref "U4") (pin "4") (pinfunction "GND_4") (pintype "power_in"))
      (node (ref "U4") (pin "6") (pinfunction "QSTRT_6") (pintype "input"))
      (node (ref "U4") (pin "9") (pinfunction "EP_9") (pintype "power_in"))
      (node (ref "U5") (pin "4") (pinfunction "GND_4") (pintype "power_in"))
      (node (ref "U5") (pin "9") (pinfunction "EXP_9") (pintype "passive"))
      (node (ref "U6") (pin "1") (pinfunction "GND_1") (pintype "power_in"))
      (node (ref "U6") (pin "5") (pinfunction "SDO_5") (pintype "bidirectional"))
      (node (ref "U6") (pin "7") (pinfunction "GND_7") (pintype "power_in"))
    )
    (net (code "14") (name "GPIO8") (class "Default")
      (node (ref "R1") (pin "1") (pinfunction "1_1") (pintype "passive"))
      (node (ref "U1") (pin "10") (pinfunction "IO8_10") (pintype "bidirectional"))
    )
    (net (code "15") (name "I2C_PW") (class "Default")
      (node (ref "C1") (pin "1") (pinfunction "1_1") (pintype "passive"))
      (node (ref "C2") (pin "1") (pinfunction "1_1") (pintype "passive"))
      (node (ref "R1_PINH") (pin "2") (pinfunction "2_2") (pintype "passive"))
      (node (ref "R2_PINH") (pin "2") (pinfunction "2_2") (pintype "passive"))
      (node (ref "U1") (pin "17") (pinfunction "IO19_17") (pintype "bidirectional"))
      (node (ref "U6") (pin "2") (pinfunction "CSB_2") (pintype "input"))
      (node (ref "U6") (pin "6") (pinfunction "VDDIO_6") (pintype "power_in"))
      (node (ref "U6") (pin "8") (pinfunction "VDD_8") (pintype "power_in"))
    )
    (net (code "16") (name "INT_RTC") (class "Default")
      (node (ref "R1_PINH1") (pin "1") (pinfunction "1_1") (pintype "passive"))
      (node (ref "TP15") (pin "TP") (pinfunction "TP_TP") (pintype "input"))
      (node (ref "U1") (pin "8") (pinfunction "IO0_8") (pintype "bidirectional"))
      (node (ref "U3") (pin "3") (pinfunction "SQW/~{INT}_3") (pintype "output"))
    )
    (net (code "17") (name "IO{slash}BOOT") (class "Default")
      (node (ref "BOOT_BUTTON") (pin "3") (pinfunction "3_3") (pintype "passive"))
      (node (ref "BOOT_BUTTON") (pin "4") (pinfunction "4_4") (pintype "passive"))
      (node (ref "C6") (pin "1") (pinfunction "1_1") (pintype "passive"))
      (node (ref "R_BOOT") (pin "1") (pinfunction "1_1") (pintype "passive"))
      (node (ref "U1") (pin "15") (pinfunction "IO9_15") (pintype "bidirectional"))
    )
    (net (code "18") (name "IO{slash}CHANGE") (class "Default")
      (node (ref "C10") (pin "1") (pinfunction "1_1") (pintype "passive"))
      (node (ref "CHANGE_BUTTON") (pin "3") (pinfunction "3_3") (pintype "passive"))
      (node (ref "CHANGE_BUTTON") (pin "4") (pinfunction "4_4") (pintype "passive"))
      (node (ref "R_CHANGE") (pin "1") (pinfunction "1_1") (pintype "passive"))
      (node (ref "U1") (pin "23") (pinfunction "IO15_23") (pintype "bidirectional"))
    )
    (net (code "19") (name "MISO") (class "Default")
      (node (ref "D12") (pin "2") (pinfunction "2_2") (pintype "passive"))
      (node (ref "J4") (pin "P7") (pinfunction "DAT0_P7") (pintype "bidirectional"))
      (node (ref "R8") (pin "1") (pinfunction "1_1") (pintype "passive"))
      (node (ref "TP6") (pin "TP") (pinfunction "TP_TP") (pintype "input"))
      (node (ref "U1") (pin "27") (pinfunction "IO2_27") (pintype "bidirectional"))
      (node (ref "U5") (pin "2") (pinfunction "DO(IO1)_2") (pintype "bidirectional"))
    )
    (net (code "20") (name "MOSI") (class "Default")
      (node (ref "D11") (pin "2") (pinfunction "2_2") (pintype "passive"))
      (node (ref "J1") (pin "14") (pinfunction "14_14") (pintype "bidirectional"))
      (node (ref "J4") (pin "P3") (pinfunction "CMD_P3") (pintype "bidirectional"))
      (node (ref "R7") (pin "1") (pinfunction "1_1") (pintype "passive"))
      (node (ref "TP7") (pin "TP") (pinfunction "TP_TP") (pintype "input"))
      (node (ref "U1") (pin "7") (pinfunction "IO7_7") (pintype "bidirectional"))
      (node (ref "U5") (pin "5") (pinfunction "DI(IO0)_5") (pintype "bidirectional"))
    )
    (net (code "21") (name "Net-(CHG_LED-PadC)") (class "Default")
      (node (ref "CHG_LED") (pin "C") (pinfunction "C_C") (pintype "passive"))
      (node (ref "R1_BAT") (pin "1") (pinfunction "1_1") (pintype "passive"))
    )
    (net (code "22") (name "Net-(D2-CATHODE)") (class "Default")
      (node (ref "C1_BAT1") (pin "1") (pinfunction "1_1") (pintype "passive"))
      (node (ref "D2") (pin "1") (pinfunction "CATHODE_1") (pintype "bidirectional"))
      (node (ref "IC4") (pin "1") (pinfunction "VIN_1") (pintype "bidirectional"))
      (node (ref "IC4") (pin "3") (pinfunction "CE_3") (pintype "bidirectional"))
      (node (ref "Q1") (pin "2") (pinfunction "S_2") (pintype "bidirectional"))
    )
    (net (code "23") (name "Net-(D3-A)") (class "Default")
      (node (ref "C4") (pin "1") (pinfunction "1_1") (pintype "passive"))
      (node (ref "D3") (pin "2") (pinfunction "A_2") (pintype "bidirectional"))
      (node (ref "D4") (pin "1") (pinfunction "K_1") (pintype "bidirectional"))
    )
    (net (code "24") (name "Net-(D7-CATHODE)") (class "Default")
      (node (ref "D7") (pin "1") (pinfunction "CATHODE_1") (pintype "bidirectional"))
      (node (ref "R_CAPACITOR") (pin "1") (pinfunction "1_1") (pintype "passive"))
    )
    (net (code "25") (name "Net-(EPD_C1-Pad2)") (class "Default")
      (node (ref "EPD_C1") (pin "2") (pinfunction "2_2") (pintype "passive"))
      (node (ref "J1") (pin "4") (pinfunction "4_4") (pintype "bidirectional"))
    )
    (net (code "26") (name "Net-(EPD_C2-Pad2)") (class "Default")
      (node (ref "EPD_C2") (pin "2") (pinfunction "2_2") (pintype "passive"))
      (node (ref "J1") (pin "5") (pinfunction "5_5") (pintype "bidirectional"))
    )
    (net (code "27") (name "Net-(EPD_C6-Pad2)") (class "Default")
      (node (ref "EPD_C6") (pin "2") (pinfunction "2_2") (pintype "passive"))
      (node (ref "J1") (pin "18") (pinfunction "18_18") (pintype "bidirectional"))
    )
    (net (code "28") (name "Net-(EPD_C7-Pad2)") (class "Default")
      (node (ref "EPD_C7") (pin "2") (pinfunction "2_2") (pintype "passive"))
      (node (ref "J1") (pin "19") (pinfunction "19_19") (pintype "bidirectional"))
    )
    (net (code "29") (name "Net-(EPD_C8-Pad2)") (class "Default")
      (node (ref "EPD_C8") (pin "2") (pinfunction "2_2") (pintype "passive"))
      (node (ref "J1") (pin "20") (pinfunction "20_20") (pintype "bidirectional"))
    )
    (net (code "30") (name "Net-(EPD_C10-Pad2)") (class "Default")
      (node (ref "EPD_C10") (pin "2") (pinfunction "2_2") (pintype "passive"))
      (node (ref "J1") (pin "22") (pinfunction "22_22") (pintype "bidirectional"))
    )
    (net (code "31") (name "Net-(EPD_C12-Pad2)") (class "Default")
      (node (ref "EPD_C12") (pin "2") (pinfunction "2_2") (pintype "passive"))
      (node (ref "J1") (pin "24") (pinfunction "24_24") (pintype "bidirectional"))
    )
    (net (code "32") (name "Net-(IC2-CT)") (class "Default")
      (node (ref "C_DELAY") (pin "1") (pinfunction "1_1") (pintype "passive"))
      (node (ref "IC2") (pin "5") (pinfunction "CT_5") (pintype "bidirectional"))
    )
    (net (code "33") (name "Net-(J2-PadA5)") (class "Default")
      (node (ref "J2") (pin "A5") (pinfunction "A5_A5") (pintype "bidirectional"))
      (node (ref "R2-USB1") (pin "2") (pinfunction "2_2") (pintype "passive"))
    )
    (net (code "34") (name "Net-(J2-PadB5)") (class "Default")
      (node (ref "J2") (pin "B5") (pinfunction "B5_B5") (pintype "bidirectional"))
      (node (ref "R2-USB") (pin "1") (pinfunction "1_1") (pintype "passive"))
    )
    (net (code "35") (name "Net-(U2-PROG)") (class "Default")
      (node (ref "R2_BAT") (pin "2") (pinfunction "2_2") (pintype "passive"))
      (node (ref "U2") (pin "5") (pinfunction "PROG_5") (pintype "input"))
    )
    (net (code "36") (name "Net-(U2-STAT)") (class "Default")
      (node (ref "R1_BAT") (pin "2") (pinfunction "2_2") (pintype "passive"))
      (node (ref "U2") (pin "1") (pinfunction "STAT_1") (pintype "output"))
    )
    (net (code "37") (name "PREVGH") (class "Default")
      (node (ref "D5") (pin "1") (pinfunction "K_1") (pintype "bidirectional"))
      (node (ref "EPD_C9") (pin "2") (pinfunction "2_2") (pintype "passive"))
      (node (ref "J1") (pin "21") (pinfunction "21_21") (pintype "bidirectional"))
    )
    (net (code "38") (name "PREVGL") (class "Default")
      (node (ref "D4") (pin "2") (pinfunction "A_2") (pintype "bidirectional"))
      (node (ref "EPD_C11") (pin "2") (pinfunction "2_2") (pintype "passive"))
      (node (ref "J1") (pin "23") (pinfunction "23_23") (pintype "bidirectional"))
    )
    (net (code "39") (name "RESE") (class "Default")
      (node (ref "J1") (pin "3") (pinfunction "3_3") (pintype "bidirectional"))
      (node (ref "Q3") (pin "2") (pinfunction "S_2") (pintype "bidirectional"))
      (node (ref "R3") (pin "2") (pinfunction "2_2") (pintype "passive"))
    )
    (net (code "40") (name "RESE'") (class "Default")
      (node (ref "R2") (pin "2") (pinfunction "2_2") (pintype "passive"))
      (node (ref "R3") (pin "1") (pinfunction "1_1") (pintype "passive"))
      (node (ref "SJ1") (pin "2") (pinfunction "2_2") (pintype "passive"))
    )
    (net (code "41") (name "RESET") (class "Default")
      (node (ref "C5") (pin "1") (pinfunction "1_1") (pintype "passive"))
      (node (ref "IC2") (pin "1") (pinfunction "VOUT_1") (pintype "bidirectional"))
      (node (ref "RESET_BUTTON") (pin "3") (pinfunction "3_3") (pintype "passive"))
      (node (ref "RESET_BUTTON") (pin "4") (pinfunction "4_4") (pintype "passive"))
      (node (ref "R_RESET") (pin "1") (pinfunction "1_1") (pintype "passive"))
      (node (ref "U1") (pin "3") (pinfunction "EN_3") (pintype "input"))
    )
    (net (code "42") (name "RTC_RST") (class "Default")
      (node (ref "U1") (pin "16") (pinfunction "IO18_16") (pintype "bidirectional"))
      (node (ref "U3") (pin "4") (pinfunction "~{RST}_4") (pintype "input"))
    )
    (net (code "43") (name "RX") (class "Default")
      (node (ref "TP2") (pin "TP") (pinfunction "TP_TP") (pintype "input"))
      (node (ref "U1") (pin "24") (pinfunction "RXD0/GPIO17_24") (pintype "bidirectional"))
    )
    (net (code "44") (name "SCK") (class "Default")
      (node (ref "D10") (pin "2") (pinfunction "2_2") (pintype "passive"))
      (node (ref "J1") (pin "13") (pinfunction "13_13") (pintype "bidirectional"))
      (node (ref "J4") (pin "P5") (pinfunction "CLK_P5") (pintype "bidirectional"))
      (node (ref "R6") (pin "1") (pinfunction "1_1") (pintype "passive"))
      (node (ref "TP8") (pin "TP") (pinfunction "TP_TP") (pintype "input"))
      (node (ref "U1") (pin "6") (pinfunction "IO6_6") (pintype "bidirectional"))
      (node (ref "U5") (pin "6") (pinfunction "CLK_6") (pintype "input"))
    )
    (net (code "45") (name "SCL") (class "Default")
      (node (ref "J3") (pin "4") (pinfunction "4_4") (pintype "passive"))
      (node (ref "R2_PINH") (pin "1") (pinfunction "1_1") (pintype "passive"))
      (node (ref "U1") (pin "20") (pinfunction "IO22_20") (pintype "bidirectional"))
      (node (ref "U3") (pin "16") (pinfunction "SCL_16") (pintype "input"))
      (node (ref "U4") (pin "7") (pinfunction "SCL_7") (pintype "input"))
      (node (ref "U6") (pin "4") (pinfunction "SCK_4") (pintype "input"))
    )
    (net (code "46") (name "SDA") (class "Default")
      (node (ref "J3") (pin "3") (pinfunction "3_3") (pintype "passive"))
      (node (ref "R1_PINH") (pin "1") (pinfunction "1_1") (pintype "passive"))
      (node (ref "U1") (pin "19") (pinfunction "IO21_19") (pintype "bidirectional"))
      (node (ref "U3") (pin "15") (pinfunction "SDA_15") (pintype "bidirectional"))
      (node (ref "U4") (pin "8") (pinfunction "SDA_8") (pintype "bidirectional"))
      (node (ref "U6") (pin "3") (pinfunction "SDI_3") (pintype "bidirectional"))
    )
    (net (code "47") (name "SRC") (class "Default")
      (node (ref "C4") (pin "2") (pinfunction "2_2") (pintype "passive"))
      (node (ref "D5") (pin "2") (pinfunction "A_2") (pintype "bidirectional"))
      (node (ref "L1") (pin "P$2") (pinfunction "2_P$2") (pintype "passive"))
      (node (ref "Q3") (pin "3") (pinfunction "D_3") (pintype "bidirectional"))
    )
    (net (code "48") (name "SS_SD") (class "Default")
      (node (ref "D8") (pin "2") (pinfunction "2_2") (pintype "passive"))
      (node (ref "J4") (pin "P2") (pinfunction "CD/DAT3_P2") (pintype "bidirectional"))
      (node (ref "R10") (pin "1") (pinfunction "1_1") (pintype "passive"))
      (node (ref "U1") (pin "4") (pinfunction "IO4_4") (pintype "bidirectional"))
    )
    (net (code "49") (name "TX") (class "Default")
      (node (ref "TP1") (pin "TP") (pinfunction "TP_TP") (pintype "input"))
      (node (ref "U1") (pin "25") (pinfunction "TXD0/GPIO16_25") (pintype "bidirectional"))
    )
    (net (code "50") (name "USB_D+") (class "Default")
      (node (ref "D1") (pin "4") (pinfunction "I/O2_2_4") (pintype "bidirectional"))
      (node (ref "U1") (pin "14") (pinfunction "IO13_14") (pintype "bidirectional"))
    )
    (net (code "51") (name "USB_D-") (class "Default")
      (node (ref "D1") (pin "6") (pinfunction "I/O1_2_6") (pintype "bidirectional"))
      (node (ref "U1") (pin "13") (pinfunction "IO12_13") (pintype "bidirectional"))
    )
    (net (code "52") (name "VBAT") (class "Default")
      (node (ref "C2_BAT") (pin "1") (pinfunction "1_1") (pintype "passive"))
      (node (ref "Q1") (pin "3") (pinfunction "D_3") (pintype "bidirectional"))
      (node (ref "TP3") (pin "TP") (pinfunction "TP_TP") (pintype "input"))
      (node (ref "U2") (pin "3") (pinfunction "VBAT_3") (pintype "power_in"))
      (node (ref "U4") (pin "2") (pinfunction "CELL_2") (pintype "power_in"))
      (node (ref "U4") (pin "3") (pinfunction "VDD_3") (pintype "power_in"))
    )
    (net (code "53") (name "VBUS") (class "Default")
      (node (ref "C1_BAT") (pin "1") (pinfunction "1_1") (pintype "passive"))
      (node (ref "C4_USB") (pin "1") (pinfunction "1_1") (pintype "passive"))
      (node (ref "C5_USB") (pin "1") (pinfunction "1_1") (pintype "passive"))
      (node (ref "CHG_LED") (pin "A") (pinfunction "A_A") (pintype "passive"))
      (node (ref "D1") (pin "2") (pinfunction "GND_2") (pintype "bidirectional"))
      (node (ref "D2") (pin "2") (pinfunction "ANODE_2") (pintype "bidirectional"))
      (node (ref "PFMF.050.1") (pin "2") (pinfunction "2_2") (pintype "passive"))
      (node (ref "Q1") (pin "1") (pinfunction "G_1") (pintype "bidirectional"))
      (node (ref "R1_PWRUSB") (pin "2") (pinfunction "2_2") (pintype "passive"))
      (node (ref "TP14") (pin "TP") (pinfunction "TP_TP") (pintype "input"))
      (node (ref "U2") (pin "4") (pinfunction "VIN_4") (pintype "power_in"))
    )
    (net (code "54") (name "VRTC") (class "Default")
      (node (ref "C10_SUPERCAP") (pin "1") (pinfunction "1_1") (pintype "passive"))
      (node (ref "C8") (pin "1") (pinfunction "1_1") (pintype "passive"))
      (node (ref "R_CAPACITOR") (pin "2") (pinfunction "2_2") (pintype "passive"))
      (node (ref "U3") (pin "14") (pinfunction "VBAT_14") (pintype "power_in"))
    )
    (net (code "55") (name "VUSB") (class "Default")
      (node (ref "J2") (pin "A4") (pinfunction "A4_A4") (pintype "bidirectional"))
      (node (ref "J2") (pin "A9") (pinfunction "A9_A9") (pintype "bidirectional"))
      (node (ref "J2") (pin "B4") (pinfunction "B4_B4") (pintype "bidirectional"))
      (node (ref "J2") (pin "B9") (pinfunction "B9_B9") (pintype "bidirectional"))
      (node (ref "PFMF.050.1") (pin "1") (pinfunction "1_1") (pintype "passive"))
    )
    (net (code "56") (name "unconnected-(IC2-NC-Pad4)") (class "Default")
      (node (ref "IC2") (pin "4") (pinfunction "NC_4") (pintype "no_connect"))
    )
    (net (code "57") (name "unconnected-(IC4-NC-Pad4)") (class "Default")
      (node (ref "IC4") (pin "4") (pinfunction "NC_4") (pintype "no_connect"))
    )
    (net (code "58") (name "unconnected-(J1-Pad1)") (class "Default")
      (node (ref "J1") (pin "1") (pinfunction "1_1") (pintype "bidirectional"))
    )
    (net (code "59") (name "unconnected-(J1-Pad6)") (class "Default")
      (node (ref "J1") (pin "6") (pinfunction "6_6") (pintype "bidirectional"))
    )
    (net (code "60") (name "unconnected-(J1-Pad7)") (class "Default")
      (node (ref "J1") (pin "7") (pinfunction "7_7") (pintype "bidirectional"))
    )
    (net (code "61") (name "unconnected-(J2-PadA8)") (class "Default")
      (node (ref "J2") (pin "A8") (pinfunction "A8_A8") (pintype "bidirectional"))
    )
    (net (code "62") (name "unconnected-(J2-PadB8)") (class "Default")
      (node (ref "J2") (pin "B8") (pinfunction "B8_B8") (pintype "bidirectional"))
    )
    (net (code "63") (name "unconnected-(J4-DAT1-PadP8)") (class "Default")
      (node (ref "J4") (pin "P8") (pinfunction "DAT1_P8") (pintype "bidirectional"))
    )
    (net (code "64") (name "unconnected-(J4-DAT2-PadP1)") (class "Default")
      (node (ref "J4") (pin "P1") (pinfunction "DAT2_P1") (pintype "bidirectional"))
    )
    (net (code "65") (name "unconnected-(J4-DETECTION_1-PadS1)") (class "Default")
      (node (ref "J4") (pin "S1") (pinfunction "DETECTION_1_S1") (pintype "bidirectional"))
    )
    (net (code "66") (name "unconnected-(J4-DETECTION_2-PadS2)") (class "Default")
      (node (ref "J4") (pin "S2") (pinfunction "DETECTION_2_S2") (pintype "bidirectional"))
    )
    (net (code "67") (name "unconnected-(U1-NC-Pad22)") (class "Default")
      (node (ref "U1") (pin "22") (pinfunction "NC_22") (pintype "no_connect"))
    )
    (net (code "68") (name "unconnected-(U4-~{ALERT}-Pad5)") (class "Default")
      (node (ref "U4") (pin "5") (pinfunction "~{ALERT}_5") (pintype "output"))
    )
  )
)
